# SW6306_CCAA_EVB_V0_2_20231010.net
KiCad netlist of a schematic drawn in Altium Designer
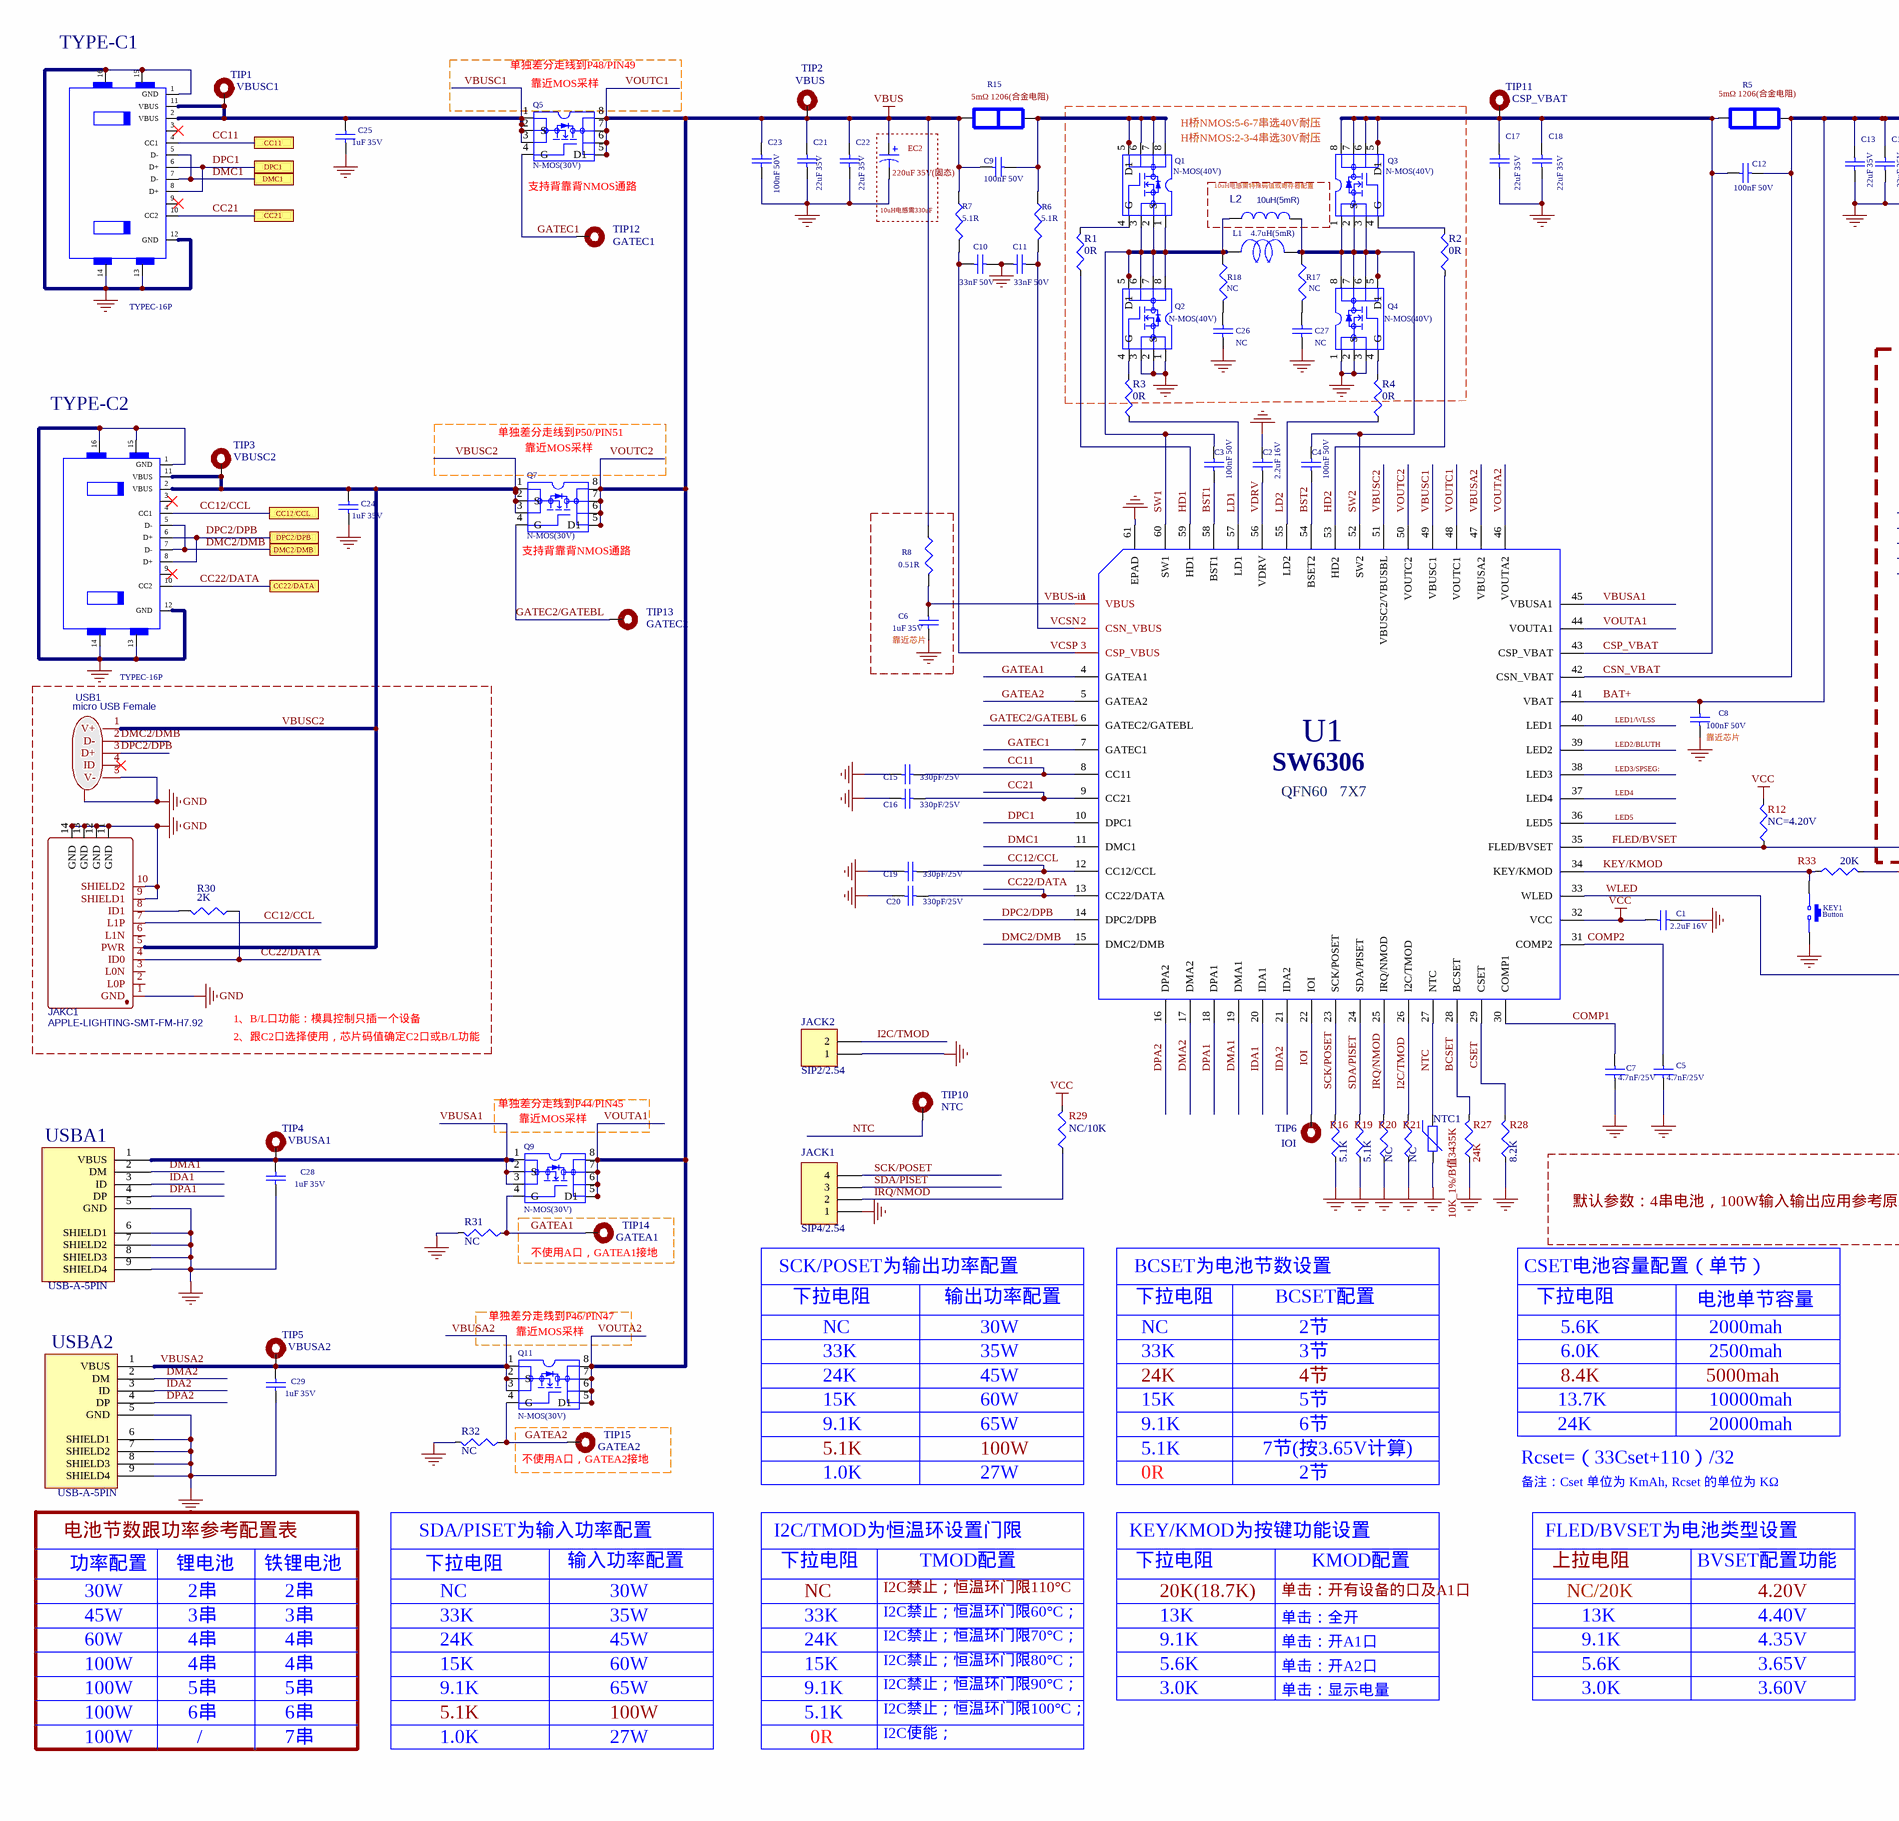
[diagram p0: SW6306_CCAA_EVB_V0.2(20231010 ).SchDoc, left]
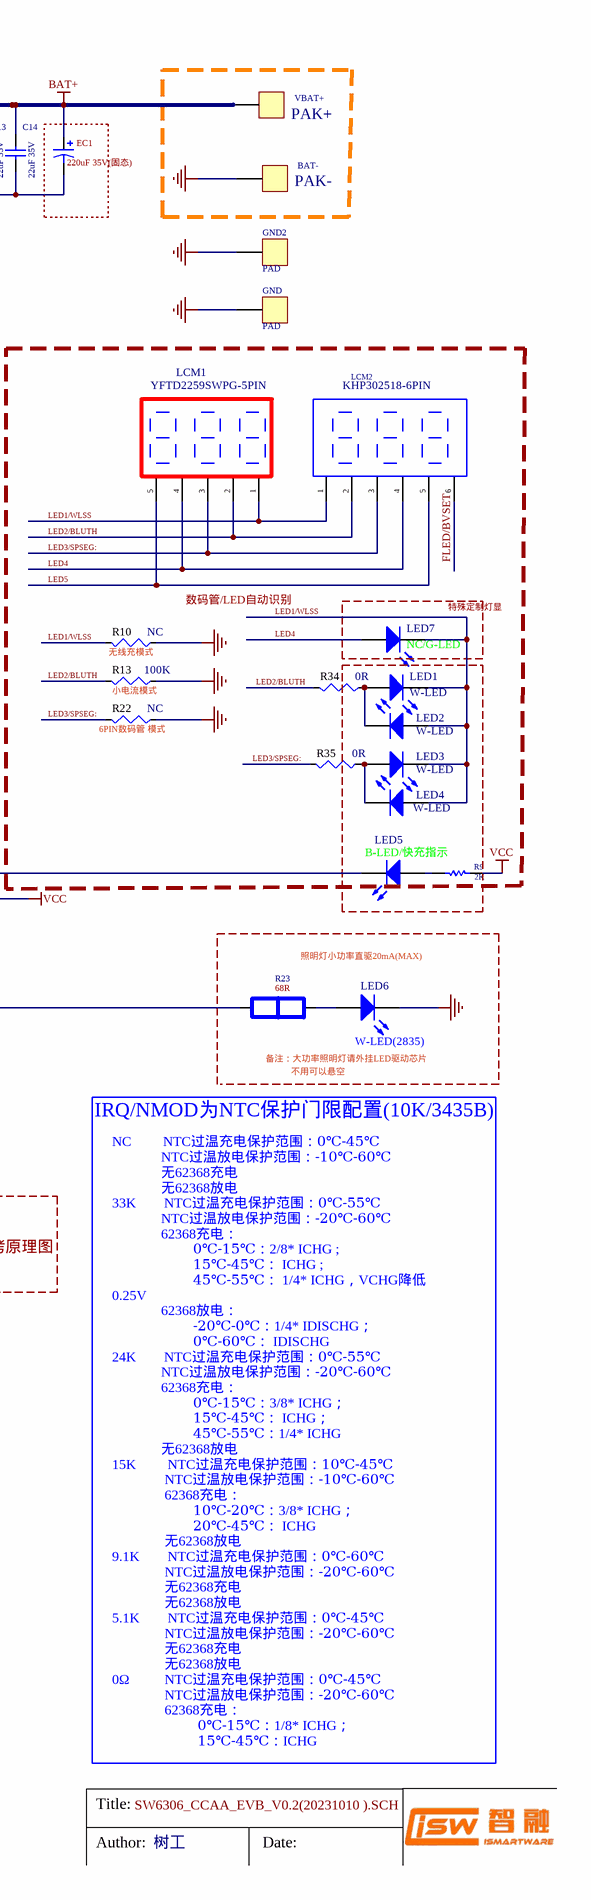
[diagram p1: SW6306_CCAA_EVB_V0.2(20231010 ).SchDoc, right]

(export (version "E")
  (design (tool "Eeschema 10.0.6"))
  (components
    (comp (ref "BAT-")
      (value "PAK-")
      (footprint "BAT-PAD")
      (description "电池包焊盘")
      (libsource (lib "") (part "PAD_1"))
    )
    (comp (ref "C1")
      (value "2.2uF 16V")
      (footprint "C 0603")
      (description "贴片电容")
      (libsource (lib "ismartware_3DLIB") (part "Capacitor"))
    )
    (comp (ref "C2")
      (value "2.2uF 16V")
      (footprint "C 0603")
      (description "贴片电容")
      (libsource (lib "ismartware_3DLIB") (part "Capacitor"))
    )
    (comp (ref "C3")
      (value "100nF 50V")
      (footprint "C 0603")
      (description "贴片电容")
      (libsource (lib "ismartware_3DLIB") (part "Capacitor"))
    )
    (comp (ref "C4")
      (value "100nF 50V")
      (footprint "C 0603")
      (description "贴片电容")
      (libsource (lib "ismartware_3DLIB") (part "Capacitor"))
    )
    (comp (ref "C5")
      (value "4.7nF/25V")
      (footprint "C 0603")
      (description "贴片电容")
      (libsource (lib "ismartware_3DLIB") (part "Capacitor"))
    )
    (comp (ref "C6")
      (value "1uF 35V")
      (footprint "C 0603")
      (description "贴片电容")
      (libsource (lib "ismartware_3DLIB") (part "Capacitor"))
    )
    (comp (ref "C7")
      (value "4.7nF/25V")
      (footprint "C 0603")
      (description "贴片电容")
      (libsource (lib "ismartware_3DLIB") (part "Capacitor"))
    )
    (comp (ref "C8")
      (value "100nF 50V")
      (footprint "C 0603")
      (description "贴片电容")
      (libsource (lib "ismartware_3DLIB") (part "Capacitor"))
    )
    (comp (ref "C9")
      (value "100nF 50V")
      (footprint "C 0603")
      (description "贴片电容")
      (libsource (lib "ismartware_3DLIB") (part "Capacitor"))
    )
    (comp (ref "C10")
      (value "33nF 50V")
      (footprint "C 0603")
      (description "贴片电容")
      (libsource (lib "ismartware_3DLIB") (part "Capacitor"))
    )
    (comp (ref "C11")
      (value "33nF 50V")
      (footprint "C 0603")
      (description "贴片电容")
      (libsource (lib "ismartware_3DLIB") (part "Capacitor"))
    )
    (comp (ref "C12")
      (value "100nF 50V")
      (footprint "C 0603")
      (description "贴片电容")
      (libsource (lib "ismartware_3DLIB") (part "Capacitor"))
    )
    (comp (ref "C13")
      (value "22uF 35V")
      (footprint "C 0805")
      (description "贴片电容")
      (libsource (lib "ismartware_3DLIB") (part "Capacitor"))
    )
    (comp (ref "C14")
      (value "22uF 35V")
      (footprint "C 0805")
      (description "贴片电容")
      (libsource (lib "ismartware_3DLIB") (part "Capacitor"))
    )
    (comp (ref "C15")
      (value "330pF/25V")
      (footprint "C 0603")
      (description "贴片电容")
      (libsource (lib "ismartware_3DLIB") (part "Capacitor"))
    )
    (comp (ref "C16")
      (value "330pF/25V")
      (footprint "C 0603")
      (description "贴片电容")
      (libsource (lib "ismartware_3DLIB") (part "Capacitor"))
    )
    (comp (ref "C17")
      (value "22uF 35V")
      (footprint "C 0805")
      (description "贴片电容")
      (libsource (lib "ismartware_3DLIB") (part "Capacitor"))
    )
    (comp (ref "C18")
      (value "22uF 35V")
      (footprint "C 0805")
      (description "贴片电容")
      (libsource (lib "ismartware_3DLIB") (part "Capacitor"))
    )
    (comp (ref "C19")
      (value "330pF/25V")
      (footprint "C 0603")
      (description "贴片电容")
      (libsource (lib "ismartware_3DLIB") (part "Capacitor"))
    )
    (comp (ref "C20")
      (value "330pF/25V")
      (footprint "C 0603")
      (description "贴片电容")
      (libsource (lib "ismartware_3DLIB") (part "Capacitor"))
    )
    (comp (ref "C21")
      (value "22uF 35V")
      (footprint "C 0805")
      (description "贴片电容")
      (libsource (lib "ismartware_3DLIB") (part "Capacitor"))
    )
    (comp (ref "C22")
      (value "22uF 35V")
      (footprint "C 0805")
      (description "贴片电容")
      (libsource (lib "ismartware_3DLIB") (part "Capacitor"))
    )
    (comp (ref "C23")
      (value "100nF 50V")
      (footprint "C 0603")
      (description "贴片电容")
      (libsource (lib "ismartware_3DLIB") (part "Capacitor"))
    )
    (comp (ref "C24")
      (value "1uF 35V")
      (footprint "C 0805")
      (description "贴片电容")
      (libsource (lib "ismartware_3DLIB") (part "Capacitor"))
    )
    (comp (ref "C25")
      (value "1uF 35V")
      (footprint "C 0805")
      (description "贴片电容")
      (libsource (lib "ismartware_3DLIB") (part "Capacitor"))
    )
    (comp (ref "C26")
      (value "NC")
      (footprint "C 0603")
      (description "贴片电容")
      (libsource (lib "Cap") (part "0603 1nF (102) 10% 50V"))
    )
    (comp (ref "C27")
      (value "NC")
      (footprint "C 0603")
      (description "贴片电容")
      (libsource (lib "Cap") (part "0603 1nF (102) 10% 50V"))
    )
    (comp (ref "C28")
      (value "1uF 35V")
      (footprint "C 0805")
      (description "贴片电容")
      (libsource (lib "ismartware_3DLIB") (part "Capacitor"))
    )
    (comp (ref "C29")
      (value "1uF 35V")
      (footprint "C 0805")
      (description "贴片电容")
      (libsource (lib "ismartware_3DLIB") (part "Capacitor"))
    )
    (comp (ref "EC1")
      (value "220uF 35V(固态)")
      (footprint "EC-6.3")
      (description "固态电容")
      (libsource (lib "ismartware_3DLIB") (part "Capacitor-E"))
    )
    (comp (ref "EC2")
      (value "220uF 35V(固态)")
      (footprint "EC-6.3")
      (description "固态电容")
      (libsource (lib "ismartware_3DLIB") (part "Capacitor-E"))
    )
    (comp (ref "GND")
      (value "PAD")
      (footprint "BAT-PAD")
      (description "单独焊盘")
      (libsource (lib "ismartware_3DLIB") (part "PAD"))
    )
    (comp (ref "GND2")
      (value "PAD")
      (footprint "BAT-PAD")
      (description "单独焊盘")
      (libsource (lib "ismartware_3DLIB") (part "PAD"))
    )
    (comp (ref "JACK1")
      (value "SIP4/2.54")
      (footprint "HDR1X4")
      (description "排针： 4Pin/2.54")
      (libsource (lib "Miscellaneous Connectors") (part "Header 4"))
    )
    (comp (ref "JACK2")
      (value "SIP2/2.54")
      (footprint "PIN2")
      (description "Header, 2-Pin, Right Angle")
      (libsource (lib "Miscellaneous Connectors") (part "Header 2H"))
    )
    (comp (ref "JAKC1")
      (value "APPLE-LIGHTING-SMT-FM-H7.92")
      (footprint "Lightning")
      (description "苹果L插座")
      (fields (field (name "BOM_SUPPLIER PART") "C168722"))
      (libsource (lib "09连接器20220524") (part "APPLE-LIGHTING-SMT-FM-H7.92"))
    )
    (comp (ref "KEY1")
      (value "Button")
      (footprint "SW-SMD-6x3.5")
      (description "贴片按键")
      (libsource (lib "*") (part "SW"))
    )
    (comp (ref "L1")
      (value "4.7uH(5mR)")
      (footprint "L 12×12")
      (description "贴片电感")
      (libsource (lib "ismartware_3DLIB") (part "Inductors"))
    )
    (comp (ref "L2")
      (value "10uH(5mR)")
      (footprint "L_环形电感_13mm")
      (description "插件环形电感")
      (libsource (lib "智融科技有限公司集成库") (part "INDUCTOR"))
    )
    (comp (ref "LCM1")
      (value "YFTD2259SWPG-5PIN")
      (footprint "LED_5PIN  12*8*4.5mm")
      (description "5PIN数码管:12*8*4.2")
      (libsource (lib "ISW_SCHLibrary") (part "LED_888_5PIN"))
    )
    (comp (ref "LCM2")
      (value "KHP302518-6PIN")
      (footprint "LED_188_6PIN")
      (description "6PIN数码管:15.3*8.15*5")
      (libsource (lib "SW6302_AAC_EVB_V0.0(20230822) ") (part "LED-888_6PIN"))
    )
    (comp (ref "LED1")
      (value "W-LED")
      (footprint "LED_0603")
      (description "贴片LED灯")
      (libsource (lib "ISW_SCHLibrary") (part "Diode-LED"))
    )
    (comp (ref "LED2")
      (value "W-LED")
      (footprint "LED_0603")
      (description "贴片LED灯")
      (libsource (lib "ISW_SCHLibrary") (part "Diode-LED"))
    )
    (comp (ref "LED3")
      (value "W-LED")
      (footprint "LED_0603")
      (description "贴片LED灯")
      (libsource (lib "ISW_SCHLibrary") (part "Diode-LED"))
    )
    (comp (ref "LED4")
      (value "W-LED")
      (footprint "LED_0603")
      (description "贴片LED灯")
      (libsource (lib "ISW_SCHLibrary") (part "Diode-LED"))
    )
    (comp (ref "LED5")
      (value "B-LED/快充指示")
      (footprint "LED_0603")
      (description "贴片LED灯")
      (libsource (lib "ISW_SCHLibrary") (part "Diode-LED"))
    )
    (comp (ref "LED6")
      (value "W-LED(2835)")
      (footprint "LED_2835")
      (description "贴片LED灯")
      (libsource (lib "ISW_SCHLibrary") (part "Diode-LED"))
    )
    (comp (ref "LED7")
      (value "NC/G-LED")
      (footprint "LED_0603")
      (description "贴片LED灯")
      (libsource (lib "ISW_SCHLibrary") (part "Diode-LED"))
    )
    (comp (ref "NTC1")
      (value "10K_1%/B值3435K")
      (footprint "R 1206")
      (description "热敏电阻")
      (libsource (lib "ISW_SCHLibrary") (part "Res Varistor"))
    )
    (comp (ref "Q1")
      (value "N-MOS(40V)")
      (footprint "PDFN-3*3")
      (description "SWT30N50")
      (libsource (lib "") (part "MOSFET-PDFN_1"))
    )
    (comp (ref "Q2")
      (value "N-MOS(40V)")
      (footprint "PDFN-3*3")
      (description "SWT30N50")
      (libsource (lib "") (part "MOSFET-PDFN_1"))
    )
    (comp (ref "Q3")
      (value "N-MOS(40V)")
      (footprint "PDFN-3*3")
      (description "SWT30N50")
      (libsource (lib "SW7203_EVB_SCH -0630") (part "MOSFET-PDFN"))
    )
    (comp (ref "Q4")
      (value "N-MOS(40V)")
      (footprint "PDFN-3*3")
      (description "SWT30N50")
      (libsource (lib "SW7203_EVB_SCH -0630") (part "MOSFET-PDFN"))
    )
    (comp (ref "Q5")
      (value "N-MOS(30V)")
      (footprint "PDFN-3*3")
      (description "SWT30N50")
      (libsource (lib "SW7203_EVB_SCH -0630") (part "MOSFET-PDFN"))
    )
    (comp (ref "Q7")
      (value "N-MOS(30V)")
      (footprint "PDFN-3*3")
      (description "SWT30N50")
      (libsource (lib "SW7203_EVB_SCH -0630") (part "MOSFET-PDFN"))
    )
    (comp (ref "Q9")
      (value "N-MOS(30V)")
      (footprint "PDFN-3*3")
      (description "SWT30N50")
      (libsource (lib "SW7203_EVB_SCH -0630") (part "MOSFET-PDFN"))
    )
    (comp (ref "Q11")
      (value "N-MOS(30V)")
      (footprint "PDFN-3*3")
      (description "SWT30N50")
      (libsource (lib "SW7203_EVB_SCH -0630") (part "MOSFET-PDFN"))
    )
    (comp (ref "R1")
      (value "0R")
      (footprint "R 0603")
      (description "贴片电阻")
      (libsource (lib "ISW_SCHLibrary") (part "Resistance"))
    )
    (comp (ref "R2")
      (value "0R")
      (footprint "R 0603")
      (description "贴片电阻")
      (libsource (lib "ISW_SCHLibrary") (part "Resistance"))
    )
    (comp (ref "R3")
      (value "0R")
      (footprint "R 0603")
      (description "贴片电阻")
      (libsource (lib "ISW_SCHLibrary") (part "Resistance"))
    )
    (comp (ref "R4")
      (value "0R")
      (footprint "R 0603")
      (description "贴片电阻")
      (libsource (lib "ISW_SCHLibrary") (part "Resistance"))
    )
    (comp (ref "R5")
      (value "5mΩ 1206(合金电阻)")
      (footprint "R 1206")
      (description "合金电阻")
      (libsource (lib "ISW_SCHLibrary") (part "resistance-1W"))
    )
    (comp (ref "R6")
      (value "5.1R")
      (footprint "R 0603")
      (description "贴片电阻")
      (libsource (lib "SW7203-AAC") (part "0603 1KΩ (1001) 1%"))
    )
    (comp (ref "R7")
      (value "5.1R")
      (footprint "R 0603")
      (description "贴片电阻")
      (libsource (lib "SW7203-AAC") (part "0603 1KΩ (1001) 1%"))
    )
    (comp (ref "R8")
      (value "0.51R")
      (footprint "R 0603")
      (description "贴片电阻")
      (libsource (lib "SW7203-AAC") (part "0603 1KΩ (1001) 1%"))
    )
    (comp (ref "R9")
      (value "2K")
      (footprint "R 0603")
      (description "贴片电阻")
      (libsource (lib "*") (part "RES"))
    )
    (comp (ref "R10")
      (value "NC")
      (footprint "R 0603")
      (description "贴片电阻")
      (libsource (lib "ISW_SCHLibrary") (part "Resistance"))
    )
    (comp (ref "R12")
      (value "NC=4.20V")
      (footprint "R 0603")
      (description "贴片电阻")
      (libsource (lib "ISW_SCHLibrary") (part "Resistance"))
    )
    (comp (ref "R13")
      (value "100K")
      (footprint "R 0603")
      (description "贴片电阻")
      (libsource (lib "ISW_SCHLibrary") (part "Resistance"))
    )
    (comp (ref "R15")
      (value "5mΩ 1206(合金电阻)")
      (footprint "R 1206")
      (description "合金电阻")
      (libsource (lib "ISW_SCHLibrary") (part "resistance-1W"))
    )
    (comp (ref "R16")
      (value "5.1K")
      (footprint "R 0603")
      (description "贴片电阻")
      (libsource (lib "ISW_SCHLibrary") (part "Resistance"))
    )
    (comp (ref "R17")
      (value "NC")
      (footprint "R 0603")
      (description "贴片电阻")
      (libsource (lib "SW7203-AAC") (part "0603 1KΩ (1001) 1%"))
    )
    (comp (ref "R18")
      (value "NC")
      (footprint "R 0603")
      (description "贴片电阻")
      (libsource (lib "SW7203-AAC") (part "0603 1KΩ (1001) 1%"))
    )
    (comp (ref "R19")
      (value "5.1K")
      (footprint "R 0603")
      (description "贴片电阻")
      (libsource (lib "ISW_SCHLibrary") (part "Resistance"))
    )
    (comp (ref "R20")
      (value "NC")
      (footprint "R 0603")
      (description "贴片电阻")
      (libsource (lib "ISW_SCHLibrary") (part "Resistance"))
    )
    (comp (ref "R21")
      (value "NC")
      (footprint "R 0603")
      (description "贴片电阻")
      (libsource (lib "ISW_SCHLibrary") (part "Resistance"))
    )
    (comp (ref "R22")
      (value "NC")
      (footprint "R 0603")
      (description "贴片电阻")
      (libsource (lib "ISW_SCHLibrary") (part "Resistance"))
    )
    (comp (ref "R23")
      (value "68R")
      (footprint "R 0805")
      (description "贴片电阻")
      (libsource (lib "ISW_SCHLibrary") (part "resistance-1W"))
    )
    (comp (ref "R27")
      (value "24K")
      (footprint "R 0603")
      (description "贴片电阻")
      (libsource (lib "ISW_SCHLibrary") (part "Resistance"))
    )
    (comp (ref "R28")
      (value "8.2K")
      (footprint "R 0603")
      (description "贴片电阻")
      (libsource (lib "ISW_SCHLibrary") (part "Resistance"))
    )
    (comp (ref "R29")
      (value "NC/10K")
      (footprint "R 0603")
      (description "贴片电阻")
      (libsource (lib "ISW_SCHLibrary") (part "Resistance"))
    )
    (comp (ref "R30")
      (value "2K")
      (footprint "R 0603")
      (description "贴片电阻")
      (libsource (lib "05电阻电容磁珠20221207") (part "?k/1%/0603"))
    )
    (comp (ref "R31")
      (value "NC")
      (footprint "R 0603")
      (description "贴片电阻")
      (libsource (lib "ISW_SCHLibrary") (part "Resistance"))
    )
    (comp (ref "R32")
      (value "NC")
      (footprint "R 0603")
      (description "贴片电阻")
      (libsource (lib "ISW_SCHLibrary") (part "Resistance"))
    )
    (comp (ref "R33")
      (value "20K")
      (footprint "R 0603")
      (description "贴片电阻")
      (libsource (lib "ISW_SCHLibrary") (part "Resistance"))
    )
    (comp (ref "R34")
      (value "0R")
      (footprint "R 0603")
      (description "贴片电阻")
      (libsource (lib "ISW_SCHLibrary") (part "Resistance"))
    )
    (comp (ref "R35")
      (value "0R")
      (footprint "R 0603")
      (description "贴片电阻")
      (libsource (lib "ISW_SCHLibrary") (part "Resistance"))
    )
    (comp (ref "TIP1")
      (value "VBUSC1")
      (footprint "tip")
      (description "测试点")
      (libsource (lib "ISW_SCHLibrary") (part "TIP"))
    )
    (comp (ref "TIP2")
      (value "VBUS")
      (footprint "tip")
      (description "测试点")
      (libsource (lib "ISW_SCHLibrary") (part "TIP"))
    )
    (comp (ref "TIP3")
      (value "VBUSC2")
      (footprint "tip")
      (description "测试点")
      (libsource (lib "ISW_SCHLibrary") (part "TIP"))
    )
    (comp (ref "TIP4")
      (value "VBUSA1")
      (footprint "tip")
      (description "测试点")
      (libsource (lib "ISW_SCHLibrary") (part "TIP"))
    )
    (comp (ref "TIP5")
      (value "VBUSA2")
      (footprint "tip")
      (description "测试点")
      (libsource (lib "ISW_SCHLibrary") (part "TIP"))
    )
    (comp (ref "TIP6")
      (value "IOI")
      (footprint "tip")
      (description "测试点")
      (libsource (lib "ISW_SCHLibrary") (part "TIP"))
    )
    (comp (ref "TIP10")
      (value "NTC")
      (footprint "tip")
      (description "测试点")
      (libsource (lib "ISW_SCHLibrary") (part "TIP"))
    )
    (comp (ref "TIP11")
      (value "CSP_VBAT")
      (footprint "tip")
      (description "测试点")
      (libsource (lib "ISW_SCHLibrary") (part "TIP"))
    )
    (comp (ref "TIP12")
      (value "GATEC1")
      (footprint "tip")
      (description "测试点")
      (libsource (lib "ISW_SCHLibrary") (part "TIP"))
    )
    (comp (ref "TIP13")
      (value "GATEC2")
      (footprint "tip")
      (description "测试点")
      (libsource (lib "ISW_SCHLibrary") (part "TIP"))
    )
    (comp (ref "TIP14")
      (value "GATEA1")
      (footprint "tip")
      (description "测试点")
      (libsource (lib "ISW_SCHLibrary") (part "TIP"))
    )
    (comp (ref "TIP15")
      (value "GATEA2")
      (footprint "tip")
      (description "测试点")
      (libsource (lib "ISW_SCHLibrary") (part "TIP"))
    )
    (comp (ref "TYPE-C1")
      (value "TYPEC-16P")
      (footprint "USB-C_16P_M")
      (description "TYPE-C-16PIN插座")
      (libsource (lib "ZR2069_demo_CCAA_V0.2(20230615)") (part "TYPEC-16P"))
    )
    (comp (ref "TYPE-C2")
      (value "TYPEC-16P")
      (footprint "USB-C_16P_M")
      (description "TYPE-C-16PIN插座")
      (libsource (lib "ZR2069_demo_CCAA_V0.2(20230615)") (part "TYPEC-16P"))
    )
    (comp (ref "U1")
      (value "SW6306")
      (footprint "QFN-60_7X7X04P")
      (description "芯片")
      (libsource (lib "SW6306_demo_CCAA_V0.2(20230711)_1") (part "ZR2069-QFN60_7x7_AACC"))
    )
    (comp (ref "USB1")
      (value "micro USB Female")
      (footprint "MICRO-USB-SMD_5P-P0.65-H-F_C10418")
      (description "USB-Micro B插座")
      (fields
        (field (name "BOM_MANUFACTURER PART") "micro USBFemale")
        (field (name "BOM_SUPPLIER PART") "C10418")
      )
      (libsource (lib "09连接器20220524") (part "micro USB Female"))
    )
    (comp (ref "USBA1")
      (value "USB-A-5PIN")
      (footprint "USB-A_5P_SMD")
      (description "USB-A 5PIN座")
      (libsource (lib "TEST") (part "TYPEA-ID"))
    )
    (comp (ref "USBA2")
      (value "USB-A-5PIN")
      (footprint "USB-A_5P_SMD")
      (description "USB-A 5PIN座")
      (libsource (lib "TEST") (part "TYPEA-ID"))
    )
    (comp (ref "VBAT+")
      (value "PAK+")
      (footprint "BAT-PAD")
      (description "电池包焊盘")
      (libsource (lib "") (part "PAD_1"))
    )
  )
  (nets
    (net (code "1") (name "/BCSET") (class "Default")
      (node (ref "R27") (pin "2") (pinfunction "2_2") (pintype "passive"))
      (node (ref "U1") (pin "28") (pinfunction "BCSET_28") (pintype "passive"))
    )
    (net (code "2") (name "/BST1") (class "Default")
      (node (ref "C3") (pin "1") (pinfunction "1_1") (pintype "passive"))
      (node (ref "U1") (pin "58") (pinfunction "BST1_58") (pintype "passive"))
    )
    (net (code "3") (name "/BST2") (class "Default")
      (node (ref "C4") (pin "1") (pinfunction "1_1") (pintype "passive"))
      (node (ref "U1") (pin "54") (pinfunction "BSET2_54") (pintype "passive"))
    )
    (net (code "4") (name "/CC11") (class "Default")
      (node (ref "C15") (pin "1") (pinfunction "1_1") (pintype "passive"))
      (node (ref "TYPE-C1") (pin "4") (pinfunction "CC1_4") (pintype "passive"))
      (node (ref "U1") (pin "8") (pinfunction "CC11_8") (pintype "passive"))
    )
    (net (code "5") (name "/CC12{slash}CCL") (class "Default")
      (node (ref "C19") (pin "1") (pinfunction "1_1") (pintype "passive"))
      (node (ref "JAKC1") (pin "7") (pinfunction "L1P_7") (pintype "passive"))
      (node (ref "TYPE-C2") (pin "4") (pinfunction "CC1_4") (pintype "passive"))
      (node (ref "U1") (pin "12") (pinfunction "CC12/CCL_12") (pintype "passive"))
    )
    (net (code "6") (name "/CC21") (class "Default")
      (node (ref "C16") (pin "1") (pinfunction "1_1") (pintype "passive"))
      (node (ref "TYPE-C1") (pin "10") (pinfunction "CC2_10") (pintype "passive"))
      (node (ref "U1") (pin "9") (pinfunction "CC21_9") (pintype "passive"))
    )
    (net (code "7") (name "/CC22{slash}DATA") (class "Default")
      (node (ref "C20") (pin "1") (pinfunction "1_1") (pintype "passive"))
      (node (ref "JAKC1") (pin "4") (pinfunction "ID0_4") (pintype "passive"))
      (node (ref "R30") (pin "1") (pinfunction "1_1") (pintype "passive"))
      (node (ref "TYPE-C2") (pin "10") (pinfunction "CC2_10") (pintype "passive"))
      (node (ref "U1") (pin "13") (pinfunction "CC22/DATA_13") (pintype "passive"))
    )
    (net (code "8") (name "/COMP1") (class "Default")
      (node (ref "C7") (pin "1") (pinfunction "1_1") (pintype "passive"))
      (node (ref "U1") (pin "30") (pinfunction "COMP1_30") (pintype "passive"))
    )
    (net (code "9") (name "/COMP2") (class "Default")
      (node (ref "C5") (pin "1") (pinfunction "1_1") (pintype "passive"))
      (node (ref "U1") (pin "31") (pinfunction "COMP2_31") (pintype "passive"))
    )
    (net (code "10") (name "/CSET") (class "Default")
      (node (ref "R28") (pin "2") (pinfunction "2_2") (pintype "passive"))
      (node (ref "U1") (pin "29") (pinfunction "CSET_29") (pintype "passive"))
    )
    (net (code "11") (name "/CSP_VBAT") (class "Default")
      (node (ref "C12") (pin "2") (pinfunction "2_2") (pintype "passive"))
      (node (ref "C17") (pin "1") (pinfunction "1_1") (pintype "passive"))
      (node (ref "C18") (pin "1") (pinfunction "1_1") (pintype "passive"))
      (node (ref "Q3") (pin "5") (pinfunction "D1_5") (pintype "passive"))
      (node (ref "Q3") (pin "6") (pinfunction "D2_6") (pintype "passive"))
      (node (ref "Q3") (pin "7") (pinfunction "D3_7") (pintype "passive"))
      (node (ref "Q3") (pin "8") (pinfunction "D4_8") (pintype "passive"))
      (node (ref "Q3") (pin "9") (pinfunction "EPAD_9") (pintype "passive"))
      (node (ref "R5") (pin "1") (pinfunction "1_1") (pintype "passive"))
      (node (ref "TIP11") (pin "1") (pinfunction "1_1") (pintype "passive"))
      (node (ref "U1") (pin "43") (pinfunction "CSP_VBAT_43") (pintype "passive"))
    )
    (net (code "12") (name "/DMA1") (class "Default")
      (node (ref "U1") (pin "19") (pinfunction "DMA1_19") (pintype "passive"))
      (node (ref "USBA1") (pin "2") (pinfunction "DM_2") (pintype "passive"))
    )
    (net (code "13") (name "/DMA2") (class "Default")
      (node (ref "U1") (pin "17") (pinfunction "DMA2_17") (pintype "passive"))
      (node (ref "USBA2") (pin "2") (pinfunction "DM_2") (pintype "passive"))
    )
    (net (code "14") (name "/DMC1") (class "Default")
      (node (ref "TYPE-C1") (pin "5") (pinfunction "D-_5") (pintype "passive"))
      (node (ref "TYPE-C1") (pin "7") (pinfunction "D-_7") (pintype "passive"))
      (node (ref "U1") (pin "11") (pinfunction "DMC1_11") (pintype "passive"))
    )
    (net (code "15") (name "/DMC2{slash}DMB") (class "Default")
      (node (ref "TYPE-C2") (pin "5") (pinfunction "D-_5") (pintype "passive"))
      (node (ref "TYPE-C2") (pin "7") (pinfunction "D-_7") (pintype "passive"))
      (node (ref "U1") (pin "15") (pinfunction "DMC2/DMB_15") (pintype "passive"))
      (node (ref "USB1") (pin "2") (pinfunction "D-_2") (pintype "passive"))
    )
    (net (code "16") (name "/DPA1") (class "Default")
      (node (ref "U1") (pin "18") (pinfunction "DPA1_18") (pintype "passive"))
      (node (ref "USBA1") (pin "4") (pinfunction "DP_4") (pintype "passive"))
    )
    (net (code "17") (name "/DPA2") (class "Default")
      (node (ref "U1") (pin "16") (pinfunction "DPA2_16") (pintype "passive"))
      (node (ref "USBA2") (pin "4") (pinfunction "DP_4") (pintype "passive"))
    )
    (net (code "18") (name "/DPC1") (class "Default")
      (node (ref "TYPE-C1") (pin "6") (pinfunction "D+_6") (pintype "passive"))
      (node (ref "TYPE-C1") (pin "8") (pinfunction "D+_8") (pintype "passive"))
      (node (ref "U1") (pin "10") (pinfunction "DPC1_10") (pintype "passive"))
    )
    (net (code "19") (name "/DPC2{slash}DPB") (class "Default")
      (node (ref "TYPE-C2") (pin "6") (pinfunction "D+_6") (pintype "passive"))
      (node (ref "TYPE-C2") (pin "8") (pinfunction "D+_8") (pintype "passive"))
      (node (ref "U1") (pin "14") (pinfunction "DPC2/DPB_14") (pintype "passive"))
      (node (ref "USB1") (pin "3") (pinfunction "D+_3") (pintype "passive"))
    )
    (net (code "20") (name "/FLED{slash}BVSET") (class "Default")
      (node (ref "LCM2") (pin "6") (pinfunction "6_6") (pintype "passive"))
      (node (ref "LED5") (pin "2") (pinfunction "K_2") (pintype "passive"))
      (node (ref "R12") (pin "1") (pinfunction "1_1") (pintype "passive"))
      (node (ref "U1") (pin "35") (pinfunction "FLED/BVSET_35") (pintype "passive"))
    )
    (net (code "21") (name "/GATEA1") (class "Default")
      (node (ref "Q9") (pin "4") (pinfunction "G_4") (pintype "passive"))
      (node (ref "R31") (pin "1") (pinfunction "1_1") (pintype "passive"))
      (node (ref "TIP14") (pin "1") (pinfunction "1_1") (pintype "passive"))
      (node (ref "U1") (pin "4") (pinfunction "GATEA1_4") (pintype "passive"))
    )
    (net (code "22") (name "/GATEA2") (class "Default")
      (node (ref "Q11") (pin "4") (pinfunction "G_4") (pintype "passive"))
      (node (ref "R32") (pin "1") (pinfunction "1_1") (pintype "passive"))
      (node (ref "TIP15") (pin "1") (pinfunction "1_1") (pintype "passive"))
      (node (ref "U1") (pin "5") (pinfunction "GATEA2_5") (pintype "passive"))
    )
    (net (code "23") (name "/GATEC1") (class "Default")
      (node (ref "Q5") (pin "4") (pinfunction "G_4") (pintype "passive"))
      (node (ref "TIP12") (pin "1") (pinfunction "1_1") (pintype "passive"))
      (node (ref "U1") (pin "7") (pinfunction "GATEC1_7") (pintype "passive"))
    )
    (net (code "24") (name "/GATEC2{slash}GATEBL") (class "Default")
      (node (ref "Q7") (pin "4") (pinfunction "G_4") (pintype "passive"))
      (node (ref "TIP13") (pin "1") (pinfunction "1_1") (pintype "passive"))
      (node (ref "U1") (pin "6") (pinfunction "GATEC2/GATEBL_6") (pintype "passive"))
    )
    (net (code "25") (name "/HD1") (class "Default")
      (node (ref "R1") (pin "1") (pinfunction "1_1") (pintype "passive"))
      (node (ref "U1") (pin "59") (pinfunction "HD1_59") (pintype "passive"))
    )
    (net (code "26") (name "/HD2") (class "Default")
      (node (ref "R2") (pin "1") (pinfunction "1_1") (pintype "passive"))
      (node (ref "U1") (pin "53") (pinfunction "HD2_53") (pintype "passive"))
    )
    (net (code "27") (name "/I2C{slash}TMOD") (class "Default")
      (node (ref "JACK2") (pin "2") (pinfunction "2_2") (pintype "passive"))
      (node (ref "R21") (pin "2") (pinfunction "2_2") (pintype "passive"))
      (node (ref "U1") (pin "26") (pinfunction "I2C/TMOD_26") (pintype "passive"))
    )
    (net (code "28") (name "/IDA1") (class "Default")
      (node (ref "U1") (pin "20") (pinfunction "IDA1_20") (pintype "passive"))
      (node (ref "USBA1") (pin "3") (pinfunction "ID_3") (pintype "passive"))
    )
    (net (code "29") (name "/IDA2") (class "Default")
      (node (ref "U1") (pin "21") (pinfunction "IDA2_21") (pintype "passive"))
      (node (ref "USBA2") (pin "3") (pinfunction "ID_3") (pintype "passive"))
    )
    (net (code "30") (name "/IOI") (class "Default")
      (node (ref "TIP6") (pin "1") (pinfunction "1_1") (pintype "passive"))
      (node (ref "U1") (pin "22") (pinfunction "IOI_22") (pintype "passive"))
    )
    (net (code "31") (name "/IRQ{slash}NMOD") (class "Default")
      (node (ref "JACK1") (pin "2") (pinfunction "2_2") (pintype "passive"))
      (node (ref "R20") (pin "2") (pinfunction "2_2") (pintype "passive"))
      (node (ref "R29") (pin "1") (pinfunction "1_1") (pintype "passive"))
      (node (ref "U1") (pin "25") (pinfunction "IRQ/NMOD_25") (pintype "passive"))
    )
    (net (code "32") (name "/KEY{slash}KMOD") (class "Default")
      (node (ref "KEY1") (pin "2") (pinfunction "2_2") (pintype "passive"))
      (node (ref "R33") (pin "1") (pinfunction "1_1") (pintype "passive"))
      (node (ref "U1") (pin "34") (pinfunction "KEY/KMOD_34") (pintype "passive"))
    )
    (net (code "33") (name "/LD1") (class "Default")
      (node (ref "R3") (pin "1") (pinfunction "1_1") (pintype "passive"))
      (node (ref "U1") (pin "57") (pinfunction "LD1_57") (pintype "passive"))
    )
    (net (code "34") (name "/LD2") (class "Default")
      (node (ref "R4") (pin "1") (pinfunction "1_1") (pintype "passive"))
      (node (ref "U1") (pin "55") (pinfunction "LD2_55") (pintype "passive"))
    )
    (net (code "35") (name "/LED1{slash}WLSS") (class "Default")
      (node (ref "LCM1") (pin "1") (pinfunction "1_1") (pintype "passive"))
      (node (ref "LCM2") (pin "1") (pinfunction "1_1") (pintype "passive"))
      (node (ref "LED1") (pin "2") (pinfunction "K_2") (pintype "passive"))
      (node (ref "LED2") (pin "1") (pinfunction "A_1") (pintype "passive"))
      (node (ref "LED3") (pin "2") (pinfunction "K_2") (pintype "passive"))
      (node (ref "LED4") (pin "1") (pinfunction "A_1") (pintype "passive"))
      (node (ref "LED7") (pin "2") (pinfunction "K_2") (pintype "passive"))
      (node (ref "R10") (pin "2") (pinfunction "2_2") (pintype "passive"))
      (node (ref "U1") (pin "40") (pinfunction "LED1_40") (pintype "passive"))
    )
    (net (code "36") (name "/LED2{slash}BLUTH") (class "Default")
      (node (ref "LCM1") (pin "2") (pinfunction "2_2") (pintype "passive"))
      (node (ref "LCM2") (pin "2") (pinfunction "2_2") (pintype "passive"))
      (node (ref "R13") (pin "2") (pinfunction "2_2") (pintype "passive"))
      (node (ref "R34") (pin "2") (pinfunction "2_2") (pintype "passive"))
      (node (ref "U1") (pin "39") (pinfunction "LED2_39") (pintype "passive"))
    )
    (net (code "37") (name "/LED3{slash}SPSEG:") (class "Default")
      (node (ref "LCM1") (pin "3") (pinfunction "3_3") (pintype "passive"))
      (node (ref "LCM2") (pin "3") (pinfunction "3_3") (pintype "passive"))
      (node (ref "R22") (pin "2") (pinfunction "2_2") (pintype "passive"))
      (node (ref "R35") (pin "2") (pinfunction "2_2") (pintype "passive"))
      (node (ref "U1") (pin "38") (pinfunction "LED3_38") (pintype "passive"))
    )
    (net (code "38") (name "/LED4") (class "Default")
      (node (ref "LCM1") (pin "4") (pinfunction "4_4") (pintype "passive"))
      (node (ref "LCM2") (pin "4") (pinfunction "4_4") (pintype "passive"))
      (node (ref "LED7") (pin "1") (pinfunction "A_1") (pintype "passive"))
      (node (ref "U1") (pin "37") (pinfunction "LED4_37") (pintype "passive"))
    )
    (net (code "39") (name "/LED5") (class "Default")
      (node (ref "LCM1") (pin "5") (pinfunction "5_5") (pintype "passive"))
      (node (ref "LCM2") (pin "5") (pinfunction "5_5") (pintype "passive"))
      (node (ref "U1") (pin "36") (pinfunction "LED5_36") (pintype "passive"))
    )
    (net (code "40") (name "/NTC") (class "Default")
      (node (ref "NTC1") (pin "1") (pinfunction "1_1") (pintype "passive"))
      (node (ref "TIP10") (pin "1") (pinfunction "1_1") (pintype "passive"))
      (node (ref "U1") (pin "27") (pinfunction "NTC_27") (pintype "passive"))
    )
    (net (code "41") (name "/SCK{slash}POSET") (class "Default")
      (node (ref "JACK1") (pin "4") (pinfunction "4_4") (pintype "passive"))
      (node (ref "R16") (pin "2") (pinfunction "2_2") (pintype "passive"))
      (node (ref "U1") (pin "23") (pinfunction "SCK/POSET_23") (pintype "passive"))
    )
    (net (code "42") (name "/SDA{slash}PISET") (class "Default")
      (node (ref "JACK1") (pin "3") (pinfunction "3_3") (pintype "passive"))
      (node (ref "R19") (pin "2") (pinfunction "2_2") (pintype "passive"))
      (node (ref "U1") (pin "24") (pinfunction "SDA/PISET_24") (pintype "passive"))
    )
    (net (code "43") (name "/SW1") (class "Default")
      (node (ref "C3") (pin "2") (pinfunction "2_2") (pintype "passive"))
      (node (ref "L1") (pin "2") (pinfunction "2_2") (pintype "passive"))
      (node (ref "L2") (pin "1") (pinfunction "1_1") (pintype "passive"))
      (node (ref "Q1") (pin "1") (pinfunction "S1_1") (pintype "passive"))
      (node (ref "Q1") (pin "2") (pinfunction "S_2") (pintype "passive"))
      (node (ref "Q1") (pin "3") (pinfunction "S3_3") (pintype "passive"))
      (node (ref "Q2") (pin "5") (pinfunction "D1_5") (pintype "passive"))
      (node (ref "Q2") (pin "6") (pinfunction "D2_6") (pintype "passive"))
      (node (ref "Q2") (pin "7") (pinfunction "D3_7") (pintype "passive"))
      (node (ref "Q2") (pin "8") (pinfunction "D4_8") (pintype "passive"))
      (node (ref "Q2") (pin "9") (pinfunction "EPAD_9") (pintype "passive"))
      (node (ref "R18") (pin "1") (pinfunction "1_1") (pintype "passive"))
      (node (ref "U1") (pin "60") (pinfunction "SW1_60") (pintype "passive"))
    )
    (net (code "44") (name "/SW2") (class "Default")
      (node (ref "C4") (pin "2") (pinfunction "2_2") (pintype "passive"))
      (node (ref "L1") (pin "1") (pinfunction "1_1") (pintype "passive"))
      (node (ref "L2") (pin "2") (pinfunction "2_2") (pintype "passive"))
      (node (ref "Q3") (pin "1") (pinfunction "S1_1") (pintype "passive"))
      (node (ref "Q3") (pin "2") (pinfunction "S_2") (pintype "passive"))
      (node (ref "Q3") (pin "3") (pinfunction "S3_3") (pintype "passive"))
      (node (ref "Q4") (pin "5") (pinfunction "D1_5") (pintype "passive"))
      (node (ref "Q4") (pin "6") (pinfunction "D2_6") (pintype "passive"))
      (node (ref "Q4") (pin "7") (pinfunction "D3_7") (pintype "passive"))
      (node (ref "Q4") (pin "8") (pinfunction "D4_8") (pintype "passive"))
      (node (ref "Q4") (pin "9") (pinfunction "EPAD_9") (pintype "passive"))
      (node (ref "R17") (pin "1") (pinfunction "1_1") (pintype "passive"))
      (node (ref "U1") (pin "52") (pinfunction "SW2_52") (pintype "passive"))
    )
    (net (code "45") (name "/VBUS-in") (class "Default")
      (node (ref "C6") (pin "1") (pinfunction "1_1") (pintype "passive"))
      (node (ref "R8") (pin "2") (pinfunction "2_2") (pintype "passive"))
      (node (ref "U1") (pin "1") (pinfunction "VBUS_1") (pintype "passive"))
    )
    (net (code "46") (name "/VBUSA1") (class "Default")
      (node (ref "C28") (pin "1") (pinfunction "1_1") (pintype "passive"))
      (node (ref "Q9") (pin "1") (pinfunction "S1_1") (pintype "passive"))
      (node (ref "Q9") (pin "2") (pinfunction "S_2") (pintype "passive"))
      (node (ref "Q9") (pin "3") (pinfunction "S3_3") (pintype "passive"))
      (node (ref "TIP4") (pin "1") (pinfunction "1_1") (pintype "passive"))
      (node (ref "U1") (pin "45") (pinfunction "VBUSA1_45") (pintype "passive"))
      (node (ref "USBA1") (pin "1") (pinfunction "VBUS_1") (pintype "passive"))
    )
    (net (code "47") (name "/VBUSA2") (class "Default")
      (node (ref "C29") (pin "1") (pinfunction "1_1") (pintype "passive"))
      (node (ref "Q11") (pin "1") (pinfunction "S1_1") (pintype "passive"))
      (node (ref "Q11") (pin "2") (pinfunction "S_2") (pintype "passive"))
      (node (ref "Q11") (pin "3") (pinfunction "S3_3") (pintype "passive"))
      (node (ref "TIP5") (pin "1") (pinfunction "1_1") (pintype "passive"))
      (node (ref "U1") (pin "47") (pinfunction "VBUSA2_47") (pintype "passive"))
      (node (ref "USBA2") (pin "1") (pinfunction "VBUS_1") (pintype "passive"))
    )
    (net (code "48") (name "/VBUSC1") (class "Default")
      (node (ref "C25") (pin "1") (pinfunction "1_1") (pintype "passive"))
      (node (ref "Q5") (pin "1") (pinfunction "S1_1") (pintype "passive"))
      (node (ref "Q5") (pin "2") (pinfunction "S_2") (pintype "passive"))
      (node (ref "Q5") (pin "3") (pinfunction "S3_3") (pintype "passive"))
      (node (ref "TIP1") (pin "1") (pinfunction "1_1") (pintype "passive"))
      (node (ref "TYPE-C1") (pin "11") (pinfunction "VBUS_11") (pintype "passive"))
      (node (ref "TYPE-C1") (pin "2") (pinfunction "VBUS_2") (pintype "passive"))
      (node (ref "U1") (pin "49") (pinfunction "VBUSC1_49") (pintype "passive"))
    )
    (net (code "49") (name "/VBUSC2") (class "Default")
      (node (ref "C24") (pin "1") (pinfunction "1_1") (pintype "passive"))
      (node (ref "JAKC1") (pin "5") (pinfunction "PWR_5") (pintype "passive"))
      (node (ref "Q7") (pin "1") (pinfunction "S1_1") (pintype "passive"))
      (node (ref "Q7") (pin "2") (pinfunction "S_2") (pintype "passive"))
      (node (ref "Q7") (pin "3") (pinfunction "S3_3") (pintype "passive"))
      (node (ref "TIP3") (pin "1") (pinfunction "1_1") (pintype "passive"))
      (node (ref "TYPE-C2") (pin "11") (pinfunction "VBUS_11") (pintype "passive"))
      (node (ref "TYPE-C2") (pin "2") (pinfunction "VBUS_2") (pintype "passive"))
      (node (ref "U1") (pin "51") (pinfunction "VBUSC2/VBUSBL_51") (pintype "passive"))
      (node (ref "USB1") (pin "1") (pinfunction "V+_1") (pintype "passive"))
    )
    (net (code "50") (name "/VCSN") (class "Default")
      (node (ref "C11") (pin "1") (pinfunction "1_1") (pintype "passive"))
      (node (ref "R6") (pin "2") (pinfunction "2_2") (pintype "passive"))
      (node (ref "U1") (pin "2") (pinfunction "CSN_VBUS_2") (pintype "passive"))
    )
    (net (code "51") (name "/VCSP") (class "Default")
      (node (ref "C10") (pin "2") (pinfunction "2_2") (pintype "passive"))
      (node (ref "R7") (pin "2") (pinfunction "2_2") (pintype "passive"))
      (node (ref "U1") (pin "3") (pinfunction "CSP_VBUS_3") (pintype "passive"))
    )
    (net (code "52") (name "/VDRV") (class "Default")
      (node (ref "C2") (pin "1") (pinfunction "1_1") (pintype "passive"))
      (node (ref "U1") (pin "56") (pinfunction "VDRV_56") (pintype "passive"))
    )
    (net (code "53") (name "/WLED") (class "Default")
      (node (ref "R23") (pin "2") (pinfunction "2_2") (pintype "passive"))
      (node (ref "U1") (pin "33") (pinfunction "WLED_33") (pintype "passive"))
    )
    (net (code "54") (name "BAT+") (class "Default")
      (node (ref "C12") (pin "1") (pinfunction "1_1") (pintype "passive"))
      (node (ref "C13") (pin "1") (pinfunction "1_1") (pintype "passive"))
      (node (ref "C14") (pin "1") (pinfunction "1_1") (pintype "passive"))
      (node (ref "C8") (pin "1") (pinfunction "1_1") (pintype "passive"))
      (node (ref "EC1") (pin "1") (pinfunction "1_1") (pintype "passive"))
      (node (ref "R5") (pin "2") (pinfunction "2_2") (pintype "passive"))
      (node (ref "U1") (pin "41") (pinfunction "VBAT_41") (pintype "passive"))
      (node (ref "U1") (pin "42") (pinfunction "CSN_VBAT_42") (pintype "passive"))
      (node (ref "VBAT+") (pin "1") (pinfunction "PAD_1") (pintype "passive"))
    )
    (net (code "55") (name "GND") (class "Default")
      (node (ref "BAT-") (pin "1") (pinfunction "PAD_1") (pintype "passive"))
      (node (ref "C1") (pin "1") (pinfunction "1_1") (pintype "passive"))
      (node (ref "C10") (pin "1") (pinfunction "1_1") (pintype "passive"))
      (node (ref "C11") (pin "2") (pinfunction "2_2") (pintype "passive"))
      (node (ref "C13") (pin "2") (pinfunction "2_2") (pintype "passive"))
      (node (ref "C14") (pin "2") (pinfunction "2_2") (pintype "passive"))
      (node (ref "C15") (pin "2") (pinfunction "2_2") (pintype "passive"))
      (node (ref "C16") (pin "2") (pinfunction "2_2") (pintype "passive"))
      (node (ref "C17") (pin "2") (pinfunction "2_2") (pintype "passive"))
      (node (ref "C18") (pin "2") (pinfunction "2_2") (pintype "passive"))
      (node (ref "C19") (pin "2") (pinfunction "2_2") (pintype "passive"))
      (node (ref "C2") (pin "2") (pinfunction "2_2") (pintype "passive"))
      (node (ref "C20") (pin "2") (pinfunction "2_2") (pintype "passive"))
      (node (ref "C21") (pin "2") (pinfunction "2_2") (pintype "passive"))
      (node (ref "C22") (pin "2") (pinfunction "2_2") (pintype "passive"))
      (node (ref "C23") (pin "2") (pinfunction "2_2") (pintype "passive"))
      (node (ref "C24") (pin "2") (pinfunction "2_2") (pintype "passive"))
      (node (ref "C25") (pin "2") (pinfunction "2_2") (pintype "passive"))
      (node (ref "C26") (pin "1") (pinfunction "1_1") (pintype "passive"))
      (node (ref "C27") (pin "1") (pinfunction "1_1") (pintype "passive"))
      (node (ref "C28") (pin "2") (pinfunction "2_2") (pintype "passive"))
      (node (ref "C29") (pin "2") (pinfunction "2_2") (pintype "passive"))
      (node (ref "C5") (pin "2") (pinfunction "2_2") (pintype "passive"))
      (node (ref "C6") (pin "2") (pinfunction "2_2") (pintype "passive"))
      (node (ref "C7") (pin "2") (pinfunction "2_2") (pintype "passive"))
      (node (ref "C8") (pin "2") (pinfunction "2_2") (pintype "passive"))
      (node (ref "EC1") (pin "2") (pinfunction "2_2") (pintype "passive"))
      (node (ref "EC2") (pin "2") (pinfunction "2_2") (pintype "passive"))
      (node (ref "GND") (pin "1") (pinfunction "PAD_1") (pintype "passive"))
      (node (ref "GND2") (pin "1") (pinfunction "PAD_1") (pintype "passive"))
      (node (ref "JACK1") (pin "1") (pinfunction "1_1") (pintype "passive"))
      (node (ref "JACK2") (pin "1") (pinfunction "1_1") (pintype "passive"))
      (node (ref "JAKC1") (pin "1") (pinfunction "GND_1") (pintype "passive"))
      (node (ref "JAKC1") (pin "10") (pinfunction "SHIELD2_10") (pintype "passive"))
      (node (ref "JAKC1") (pin "11") (pinfunction "GND_11") (pintype "passive"))
      (node (ref "JAKC1") (pin "12") (pinfunction "GND_12") (pintype "passive"))
      (node (ref "JAKC1") (pin "13") (pinfunction "GND_13") (pintype "passive"))
      (node (ref "JAKC1") (pin "14") (pinfunction "GND_14") (pintype "passive"))
      (node (ref "JAKC1") (pin "9") (pinfunction "SHIELD1_9") (pintype "passive"))
      (node (ref "KEY1") (pin "1") (pinfunction "1_1") (pintype "passive"))
      (node (ref "LED6") (pin "2") (pinfunction "K_2") (pintype "passive"))
      (node (ref "NTC1") (pin "2") (pinfunction "2_2") (pintype "passive"))
      (node (ref "Q2") (pin "1") (pinfunction "S1_1") (pintype "passive"))
      (node (ref "Q2") (pin "2") (pinfunction "S_2") (pintype "passive"))
      (node (ref "Q2") (pin "3") (pinfunction "S3_3") (pintype "passive"))
      (node (ref "Q4") (pin "1") (pinfunction "S1_1") (pintype "passive"))
      (node (ref "Q4") (pin "2") (pinfunction "S_2") (pintype "passive"))
      (node (ref "Q4") (pin "3") (pinfunction "S3_3") (pintype "passive"))
      (node (ref "R10") (pin "1") (pinfunction "1_1") (pintype "passive"))
      (node (ref "R13") (pin "1") (pinfunction "1_1") (pintype "passive"))
      (node (ref "R16") (pin "1") (pinfunction "1_1") (pintype "passive"))
      (node (ref "R19") (pin "1") (pinfunction "1_1") (pintype "passive"))
      (node (ref "R20") (pin "1") (pinfunction "1_1") (pintype "passive"))
      (node (ref "R21") (pin "1") (pinfunction "1_1") (pintype "passive"))
      (node (ref "R22") (pin "1") (pinfunction "1_1") (pintype "passive"))
      (node (ref "R27") (pin "1") (pinfunction "1_1") (pintype "passive"))
      (node (ref "R28") (pin "1") (pinfunction "1_1") (pintype "passive"))
      (node (ref "R31") (pin "2") (pinfunction "2_2") (pintype "passive"))
      (node (ref "R32") (pin "2") (pinfunction "2_2") (pintype "passive"))
      (node (ref "TYPE-C1") (pin "1") (pinfunction "GND_1") (pintype "passive"))
      (node (ref "TYPE-C1") (pin "12") (pinfunction "GND_12") (pintype "passive"))
      (node (ref "TYPE-C1") (pin "13") (pinfunction "13_13") (pintype "passive"))
      (node (ref "TYPE-C1") (pin "14") (pinfunction "14_14") (pintype "passive"))
      (node (ref "TYPE-C1") (pin "15") (pinfunction "15_15") (pintype "passive"))
      (node (ref "TYPE-C1") (pin "16") (pinfunction "16_16") (pintype "passive"))
      (node (ref "TYPE-C2") (pin "1") (pinfunction "GND_1") (pintype "passive"))
      (node (ref "TYPE-C2") (pin "12") (pinfunction "GND_12") (pintype "passive"))
      (node (ref "TYPE-C2") (pin "13") (pinfunction "13_13") (pintype "passive"))
      (node (ref "TYPE-C2") (pin "14") (pinfunction "14_14") (pintype "passive"))
      (node (ref "TYPE-C2") (pin "15") (pinfunction "15_15") (pintype "passive"))
      (node (ref "TYPE-C2") (pin "16") (pinfunction "16_16") (pintype "passive"))
      (node (ref "U1") (pin "61") (pinfunction "EPAD_61") (pintype "passive"))
      (node (ref "USB1") (pin "0") (pinfunction "MTN_0") (pintype "passive"))
      (node (ref "USB1") (pin "5") (pinfunction "V-_5") (pintype "passive"))
      (node (ref "USBA1") (pin "5") (pinfunction "GND_5") (pintype "passive"))
      (node (ref "USBA1") (pin "6") (pinfunction "SHIELD1_6") (pintype "passive"))
      (node (ref "USBA1") (pin "7") (pinfunction "SHIELD2_7") (pintype "passive"))
      (node (ref "USBA1") (pin "8") (pinfunction "SHIELD3_8") (pintype "passive"))
      (node (ref "USBA1") (pin "9") (pinfunction "SHIELD4_9") (pintype "passive"))
      (node (ref "USBA2") (pin "5") (pinfunction "GND_5") (pintype "passive"))
      (node (ref "USBA2") (pin "6") (pinfunction "SHIELD1_6") (pintype "passive"))
      (node (ref "USBA2") (pin "7") (pinfunction "SHIELD2_7") (pintype "passive"))
      (node (ref "USBA2") (pin "8") (pinfunction "SHIELD3_8") (pintype "passive"))
      (node (ref "USBA2") (pin "9") (pinfunction "SHIELD4_9") (pintype "passive"))
    )
    (net (code "56") (name "Net-(C26-Pad2)") (class "Default")
      (node (ref "C26") (pin "2") (pinfunction "2_2") (pintype "passive"))
      (node (ref "R18") (pin "2") (pinfunction "2_2") (pintype "passive"))
    )
    (net (code "57") (name "Net-(C27-Pad2)") (class "Default")
      (node (ref "C27") (pin "2") (pinfunction "2_2") (pintype "passive"))
      (node (ref "R17") (pin "2") (pinfunction "2_2") (pintype "passive"))
    )
    (net (code "58") (name "Net-(JAKC1-ID1)") (class "Default")
      (node (ref "JAKC1") (pin "8") (pinfunction "ID1_8") (pintype "passive"))
      (node (ref "R30") (pin "2") (pinfunction "2_2") (pintype "passive"))
    )
    (net (code "59") (name "Net-(LED1-A)") (class "Default")
      (node (ref "LED1") (pin "1") (pinfunction "A_1") (pintype "passive"))
      (node (ref "LED2") (pin "2") (pinfunction "K_2") (pintype "passive"))
      (node (ref "R34") (pin "1") (pinfunction "1_1") (pintype "passive"))
    )
    (net (code "60") (name "Net-(LED3-A)") (class "Default")
      (node (ref "LED3") (pin "1") (pinfunction "A_1") (pintype "passive"))
      (node (ref "LED4") (pin "2") (pinfunction "K_2") (pintype "passive"))
      (node (ref "R35") (pin "1") (pinfunction "1_1") (pintype "passive"))
    )
    (net (code "61") (name "Net-(LED5-A)") (class "Default")
      (node (ref "LED5") (pin "1") (pinfunction "A_1") (pintype "passive"))
      (node (ref "R9") (pin "1") (pinfunction "1_1") (pintype "passive"))
    )
    (net (code "62") (name "Net-(LED6-A)") (class "Default")
      (node (ref "LED6") (pin "1") (pinfunction "A_1") (pintype "passive"))
      (node (ref "R23") (pin "1") (pinfunction "1_1") (pintype "passive"))
    )
    (net (code "63") (name "Net-(Q1-D1)") (class "Default")
      (node (ref "C9") (pin "1") (pinfunction "1_1") (pintype "passive"))
      (node (ref "Q1") (pin "5") (pinfunction "D1_5") (pintype "passive"))
      (node (ref "Q1") (pin "6") (pinfunction "D2_6") (pintype "passive"))
      (node (ref "Q1") (pin "7") (pinfunction "D3_7") (pintype "passive"))
      (node (ref "Q1") (pin "8") (pinfunction "D4_8") (pintype "passive"))
      (node (ref "Q1") (pin "9") (pinfunction "EPAD_9") (pintype "passive"))
      (node (ref "R15") (pin "2") (pinfunction "2_2") (pintype "passive"))
      (node (ref "R6") (pin "1") (pinfunction "1_1") (pintype "passive"))
    )
    (net (code "64") (name "Net-(Q1-G)") (class "Default")
      (node (ref "Q1") (pin "4") (pinfunction "G_4") (pintype "passive"))
      (node (ref "R1") (pin "2") (pinfunction "2_2") (pintype "passive"))
    )
    (net (code "65") (name "Net-(Q2-G)") (class "Default")
      (node (ref "Q2") (pin "4") (pinfunction "G_4") (pintype "passive"))
      (node (ref "R3") (pin "2") (pinfunction "2_2") (pintype "passive"))
    )
    (net (code "66") (name "Net-(Q3-G)") (class "Default")
      (node (ref "Q3") (pin "4") (pinfunction "G_4") (pintype "passive"))
      (node (ref "R2") (pin "2") (pinfunction "2_2") (pintype "passive"))
    )
    (net (code "67") (name "Net-(Q4-G)") (class "Default")
      (node (ref "Q4") (pin "4") (pinfunction "G_4") (pintype "passive"))
      (node (ref "R4") (pin "2") (pinfunction "2_2") (pintype "passive"))
    )
    (net (code "68") (name "VBUS") (class "Default")
      (node (ref "C21") (pin "1") (pinfunction "1_1") (pintype "passive"))
      (node (ref "C22") (pin "1") (pinfunction "1_1") (pintype "passive"))
      (node (ref "C23") (pin "1") (pinfunction "1_1") (pintype "passive"))
      (node (ref "C9") (pin "2") (pinfunction "2_2") (pintype "passive"))
      (node (ref "EC2") (pin "1") (pinfunction "1_1") (pintype "passive"))
      (node (ref "Q11") (pin "5") (pinfunction "D1_5") (pintype "passive"))
      (node (ref "Q11") (pin "6") (pinfunction "D2_6") (pintype "passive"))
      (node (ref "Q11") (pin "7") (pinfunction "D3_7") (pintype "passive"))
      (node (ref "Q11") (pin "8") (pinfunction "D4_8") (pintype "passive"))
      (node (ref "Q11") (pin "9") (pinfunction "EPAD_9") (pintype "passive"))
      (node (ref "Q5") (pin "5") (pinfunction "D1_5") (pintype "passive"))
      (node (ref "Q5") (pin "6") (pinfunction "D2_6") (pintype "passive"))
      (node (ref "Q5") (pin "7") (pinfunction "D3_7") (pintype "passive"))
      (node (ref "Q5") (pin "8") (pinfunction "D4_8") (pintype "passive"))
      (node (ref "Q5") (pin "9") (pinfunction "EPAD_9") (pintype "passive"))
      (node (ref "Q7") (pin "5") (pinfunction "D1_5") (pintype "passive"))
      (node (ref "Q7") (pin "6") (pinfunction "D2_6") (pintype "passive"))
      (node (ref "Q7") (pin "7") (pinfunction "D3_7") (pintype "passive"))
      (node (ref "Q7") (pin "8") (pinfunction "D4_8") (pintype "passive"))
      (node (ref "Q7") (pin "9") (pinfunction "EPAD_9") (pintype "passive"))
      (node (ref "Q9") (pin "5") (pinfunction "D1_5") (pintype "passive"))
      (node (ref "Q9") (pin "6") (pinfunction "D2_6") (pintype "passive"))
      (node (ref "Q9") (pin "7") (pinfunction "D3_7") (pintype "passive"))
      (node (ref "Q9") (pin "8") (pinfunction "D4_8") (pintype "passive"))
      (node (ref "Q9") (pin "9") (pinfunction "EPAD_9") (pintype "passive"))
      (node (ref "R15") (pin "1") (pinfunction "1_1") (pintype "passive"))
      (node (ref "R7") (pin "1") (pinfunction "1_1") (pintype "passive"))
      (node (ref "R8") (pin "1") (pinfunction "1_1") (pintype "passive"))
      (node (ref "TIP2") (pin "1") (pinfunction "1_1") (pintype "passive"))
      (node (ref "U1") (pin "44") (pinfunction "VOUTA1_44") (pintype "passive"))
      (node (ref "U1") (pin "46") (pinfunction "VOUTA2_46") (pintype "passive"))
      (node (ref "U1") (pin "48") (pinfunction "VOUTC1_48") (pintype "passive"))
      (node (ref "U1") (pin "50") (pinfunction "VOUTC2_50") (pintype "passive"))
    )
    (net (code "69") (name "VCC") (class "Default")
      (node (ref "C1") (pin "2") (pinfunction "2_2") (pintype "passive"))
      (node (ref "R12") (pin "2") (pinfunction "2_2") (pintype "passive"))
      (node (ref "R29") (pin "2") (pinfunction "2_2") (pintype "passive"))
      (node (ref "R33") (pin "2") (pinfunction "2_2") (pintype "passive"))
      (node (ref "R9") (pin "2") (pinfunction "2_2") (pintype "passive"))
      (node (ref "U1") (pin "32") (pinfunction "VCC_32") (pintype "passive"))
    )
    (net (code "70") (name "unconnected-(JAKC1-L0N-Pad3)") (class "Default")
      (node (ref "JAKC1") (pin "3") (pinfunction "L0N_3") (pintype "passive"))
    )
    (net (code "71") (name "unconnected-(JAKC1-L0P-Pad2)") (class "Default")
      (node (ref "JAKC1") (pin "2") (pinfunction "L0P_2") (pintype "passive"))
    )
    (net (code "72") (name "unconnected-(JAKC1-L1N-Pad6)") (class "Default")
      (node (ref "JAKC1") (pin "6") (pinfunction "L1N_6") (pintype "passive"))
    )
    (net (code "73") (name "unconnected-(TYPE-C1-Pad3)") (class "Default")
      (node (ref "TYPE-C1") (pin "3") (pinfunction "3_3") (pintype "passive+no_connect"))
    )
    (net (code "74") (name "unconnected-(TYPE-C1-Pad9)") (class "Default")
      (node (ref "TYPE-C1") (pin "9") (pinfunction "9_9") (pintype "passive+no_connect"))
    )
    (net (code "75") (name "unconnected-(TYPE-C2-Pad3)") (class "Default")
      (node (ref "TYPE-C2") (pin "3") (pinfunction "3_3") (pintype "passive+no_connect"))
    )
    (net (code "76") (name "unconnected-(TYPE-C2-Pad9)") (class "Default")
      (node (ref "TYPE-C2") (pin "9") (pinfunction "9_9") (pintype "passive+no_connect"))
    )
    (net (code "77") (name "unconnected-(USB1-ID-Pad4)") (class "Default")
      (node (ref "USB1") (pin "4") (pinfunction "ID_4") (pintype "passive+no_connect"))
    )
  )
)
